# Ivy_Sensor_Shield.net
KiCad netlist of a schematic drawn in EAGLE
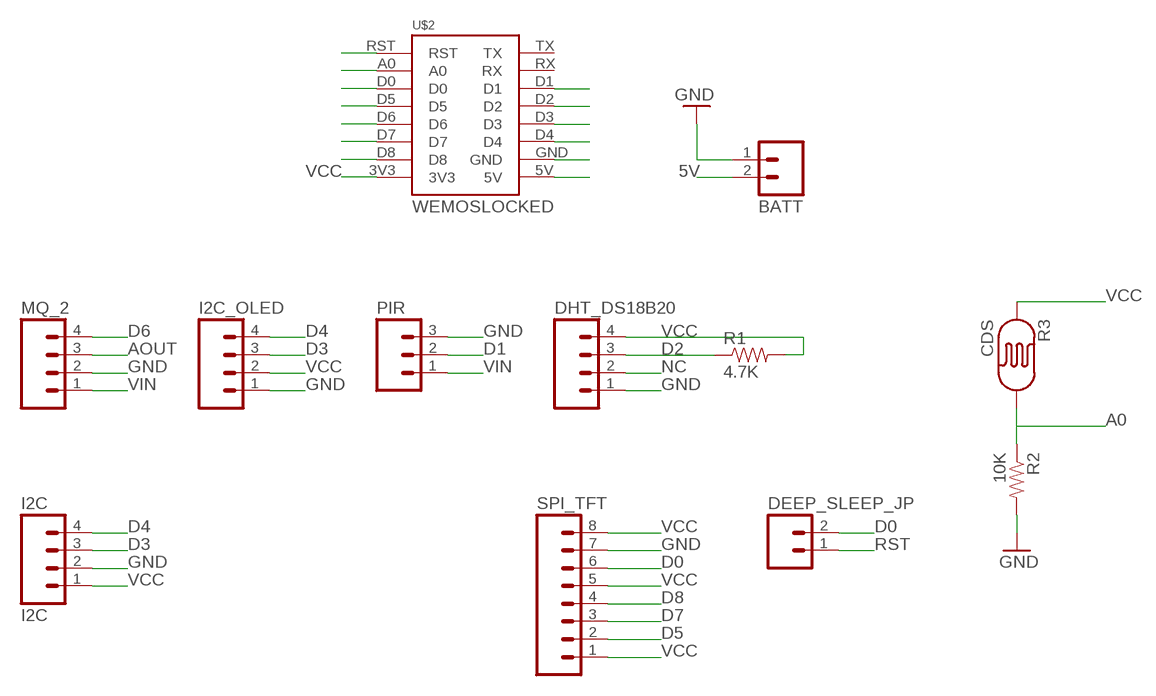
[diagram p0: schematic, sheet 1]

(export (version "E")
  (design (tool "Eeschema 10.0.6"))
  (components
    (comp (ref "BATT")
      (value "M02PTH")
      (footprint "eagle-import:1X02")
      (libsource (lib "eagle-import") (part "M02PTH"))
    )
    (comp (ref "DEEP_SLEEP_JP")
      (value "M02PTH")
      (footprint "eagle-import:1X02")
      (libsource (lib "eagle-import") (part "M02PTH"))
    )
    (comp (ref "DHT_DS18B20")
      (value "M04PTH")
      (footprint "eagle-import:1X04")
      (libsource (lib "eagle-import") (part "M04PTH"))
    )
    (comp (ref "I2C")
      (value "I2C")
      (footprint "eagle-import:1X04")
      (libsource (lib "eagle-import") (part "M04PTH"))
    )
    (comp (ref "I2C_OLED")
      (value "M04PTH")
      (footprint "eagle-import:1X04")
      (libsource (lib "eagle-import") (part "M04PTH"))
    )
    (comp (ref "MQ_2")
      (value "M04PTH")
      (footprint "eagle-import:1X04")
      (libsource (lib "eagle-import") (part "M04PTH"))
    )
    (comp (ref "PIR")
      (value "M03PTH")
      (footprint "eagle-import:1X03")
      (libsource (lib "eagle-import") (part "M03PTH"))
    )
    (comp (ref "R1")
      (value "4.7K")
      (footprint "eagle-import:0805")
      (libsource (lib "eagle-import") (part "RESISTOR0805-RES"))
    )
    (comp (ref "R2")
      (value "10K")
      (footprint "eagle-import:0805")
      (libsource (lib "eagle-import") (part "RESISTOR0805-RES"))
    )
    (comp (ref "R3")
      (value "CDS")
      (footprint "eagle-import:PHOTOCELL_THIN")
      (libsource (lib "eagle-import") (part "PHOTOCELL"))
    )
    (comp (ref "SPI_TFT")
      (value "M08")
      (footprint "eagle-import:1X08_ROUND")
      (libsource (lib "eagle-import") (part "M08"))
    )
    (comp (ref "U$2")
      (value "WEMOSLOCKED")
      (footprint "eagle-import:WEMOS_LOCKED")
      (libsource (lib "eagle-import") (part "WEMOSLOCKED"))
    )
  )
  (nets
    (net (code "1") (name "/5V") (class "Default")
      (node (ref "BATT") (pin "2") (pinfunction "2_2") (pintype "passive"))
      (node (ref "U$2") (pin "5V") (pinfunction "5V_5V") (pintype "bidirectional"))
    )
    (net (code "2") (name "/A0") (class "Default")
      (node (ref "R2") (pin "1") (pinfunction "1_1") (pintype "passive"))
      (node (ref "R3") (pin "2") (pinfunction "P$2_2") (pintype "bidirectional"))
      (node (ref "U$2") (pin "A0") (pinfunction "A0_A0") (pintype "bidirectional"))
    )
    (net (code "3") (name "/AOUT") (class "Default")
      (node (ref "MQ_2") (pin "3") (pinfunction "3_3") (pintype "passive"))
    )
    (net (code "4") (name "/D0") (class "Default")
      (node (ref "DEEP_SLEEP_JP") (pin "2") (pinfunction "2_2") (pintype "passive"))
      (node (ref "SPI_TFT") (pin "6") (pinfunction "6_6") (pintype "passive"))
      (node (ref "U$2") (pin "D0") (pinfunction "D0_D0") (pintype "bidirectional"))
    )
    (net (code "5") (name "/D1") (class "Default")
      (node (ref "PIR") (pin "2") (pinfunction "2_2") (pintype "passive"))
      (node (ref "U$2") (pin "D1") (pinfunction "D1_D1") (pintype "bidirectional"))
    )
    (net (code "6") (name "/D2") (class "Default")
      (node (ref "DHT_DS18B20") (pin "3") (pinfunction "3_3") (pintype "passive"))
      (node (ref "R1") (pin "1") (pinfunction "1_1") (pintype "passive"))
      (node (ref "U$2") (pin "D2") (pinfunction "D2_D2") (pintype "bidirectional"))
    )
    (net (code "7") (name "/D3") (class "Default")
      (node (ref "I2C") (pin "3") (pinfunction "3_3") (pintype "passive"))
      (node (ref "I2C_OLED") (pin "3") (pinfunction "3_3") (pintype "passive"))
      (node (ref "U$2") (pin "D3") (pinfunction "D3_D3") (pintype "bidirectional"))
    )
    (net (code "8") (name "/D4") (class "Default")
      (node (ref "I2C") (pin "4") (pinfunction "4_4") (pintype "passive"))
      (node (ref "I2C_OLED") (pin "4") (pinfunction "4_4") (pintype "passive"))
      (node (ref "U$2") (pin "D4") (pinfunction "D4_D4") (pintype "bidirectional"))
    )
    (net (code "9") (name "/D5") (class "Default")
      (node (ref "SPI_TFT") (pin "2") (pinfunction "2_2") (pintype "passive"))
      (node (ref "U$2") (pin "D5") (pinfunction "D5_D5") (pintype "bidirectional"))
    )
    (net (code "10") (name "/D6") (class "Default")
      (node (ref "MQ_2") (pin "4") (pinfunction "4_4") (pintype "passive"))
      (node (ref "U$2") (pin "D6") (pinfunction "D6_D6") (pintype "bidirectional"))
    )
    (net (code "11") (name "/D7") (class "Default")
      (node (ref "SPI_TFT") (pin "3") (pinfunction "3_3") (pintype "passive"))
      (node (ref "U$2") (pin "D7") (pinfunction "D7_D7") (pintype "bidirectional"))
    )
    (net (code "12") (name "/D8") (class "Default")
      (node (ref "SPI_TFT") (pin "4") (pinfunction "4_4") (pintype "passive"))
      (node (ref "U$2") (pin "D8") (pinfunction "D8_D8") (pintype "bidirectional"))
    )
    (net (code "13") (name "/NC") (class "Default")
      (node (ref "DHT_DS18B20") (pin "2") (pinfunction "2_2") (pintype "passive"))
    )
    (net (code "14") (name "/RST") (class "Default")
      (node (ref "DEEP_SLEEP_JP") (pin "1") (pinfunction "1_1") (pintype "passive"))
      (node (ref "U$2") (pin "RST") (pinfunction "RST_RST") (pintype "bidirectional"))
    )
    (net (code "15") (name "/VCC") (class "Default")
      (node (ref "DHT_DS18B20") (pin "4") (pinfunction "4_4") (pintype "passive"))
      (node (ref "I2C") (pin "1") (pinfunction "1_1") (pintype "passive"))
      (node (ref "I2C_OLED") (pin "2") (pinfunction "2_2") (pintype "passive"))
      (node (ref "R1") (pin "2") (pinfunction "2_2") (pintype "passive"))
      (node (ref "R3") (pin "1") (pinfunction "P$1_1") (pintype "bidirectional"))
      (node (ref "SPI_TFT") (pin "1") (pinfunction "1_1") (pintype "passive"))
      (node (ref "SPI_TFT") (pin "5") (pinfunction "5_5") (pintype "passive"))
      (node (ref "SPI_TFT") (pin "8") (pinfunction "8_8") (pintype "passive"))
      (node (ref "U$2") (pin "3V3") (pinfunction "3V3_3V3") (pintype "bidirectional"))
    )
    (net (code "16") (name "/VIN") (class "Default")
      (node (ref "MQ_2") (pin "1") (pinfunction "1_1") (pintype "passive"))
      (node (ref "PIR") (pin "1") (pinfunction "1_1") (pintype "passive"))
    )
    (net (code "17") (name "GND") (class "Default")
      (node (ref "BATT") (pin "1") (pinfunction "1_1") (pintype "passive"))
      (node (ref "DHT_DS18B20") (pin "1") (pinfunction "1_1") (pintype "passive"))
      (node (ref "I2C") (pin "2") (pinfunction "2_2") (pintype "passive"))
      (node (ref "I2C_OLED") (pin "1") (pinfunction "1_1") (pintype "passive"))
      (node (ref "MQ_2") (pin "2") (pinfunction "2_2") (pintype "passive"))
      (node (ref "PIR") (pin "3") (pinfunction "3_3") (pintype "passive"))
      (node (ref "R2") (pin "2") (pinfunction "2_2") (pintype "passive"))
      (node (ref "SPI_TFT") (pin "7") (pinfunction "7_7") (pintype "passive"))
      (node (ref "U$2") (pin "GND") (pinfunction "GND_GND") (pintype "bidirectional"))
    )
    (net (code "18") (name "unconnected-(U$2-PadRX)") (class "Default")
      (node (ref "U$2") (pin "RX") (pinfunction "RX_RX") (pintype "bidirectional"))
    )
    (net (code "19") (name "unconnected-(U$2-PadTX)") (class "Default")
      (node (ref "U$2") (pin "TX") (pinfunction "TX_TX") (pintype "bidirectional"))
    )
  )
)
